# CameraSliderV1.net
KiCad netlist of a schematic drawn in EAGLE
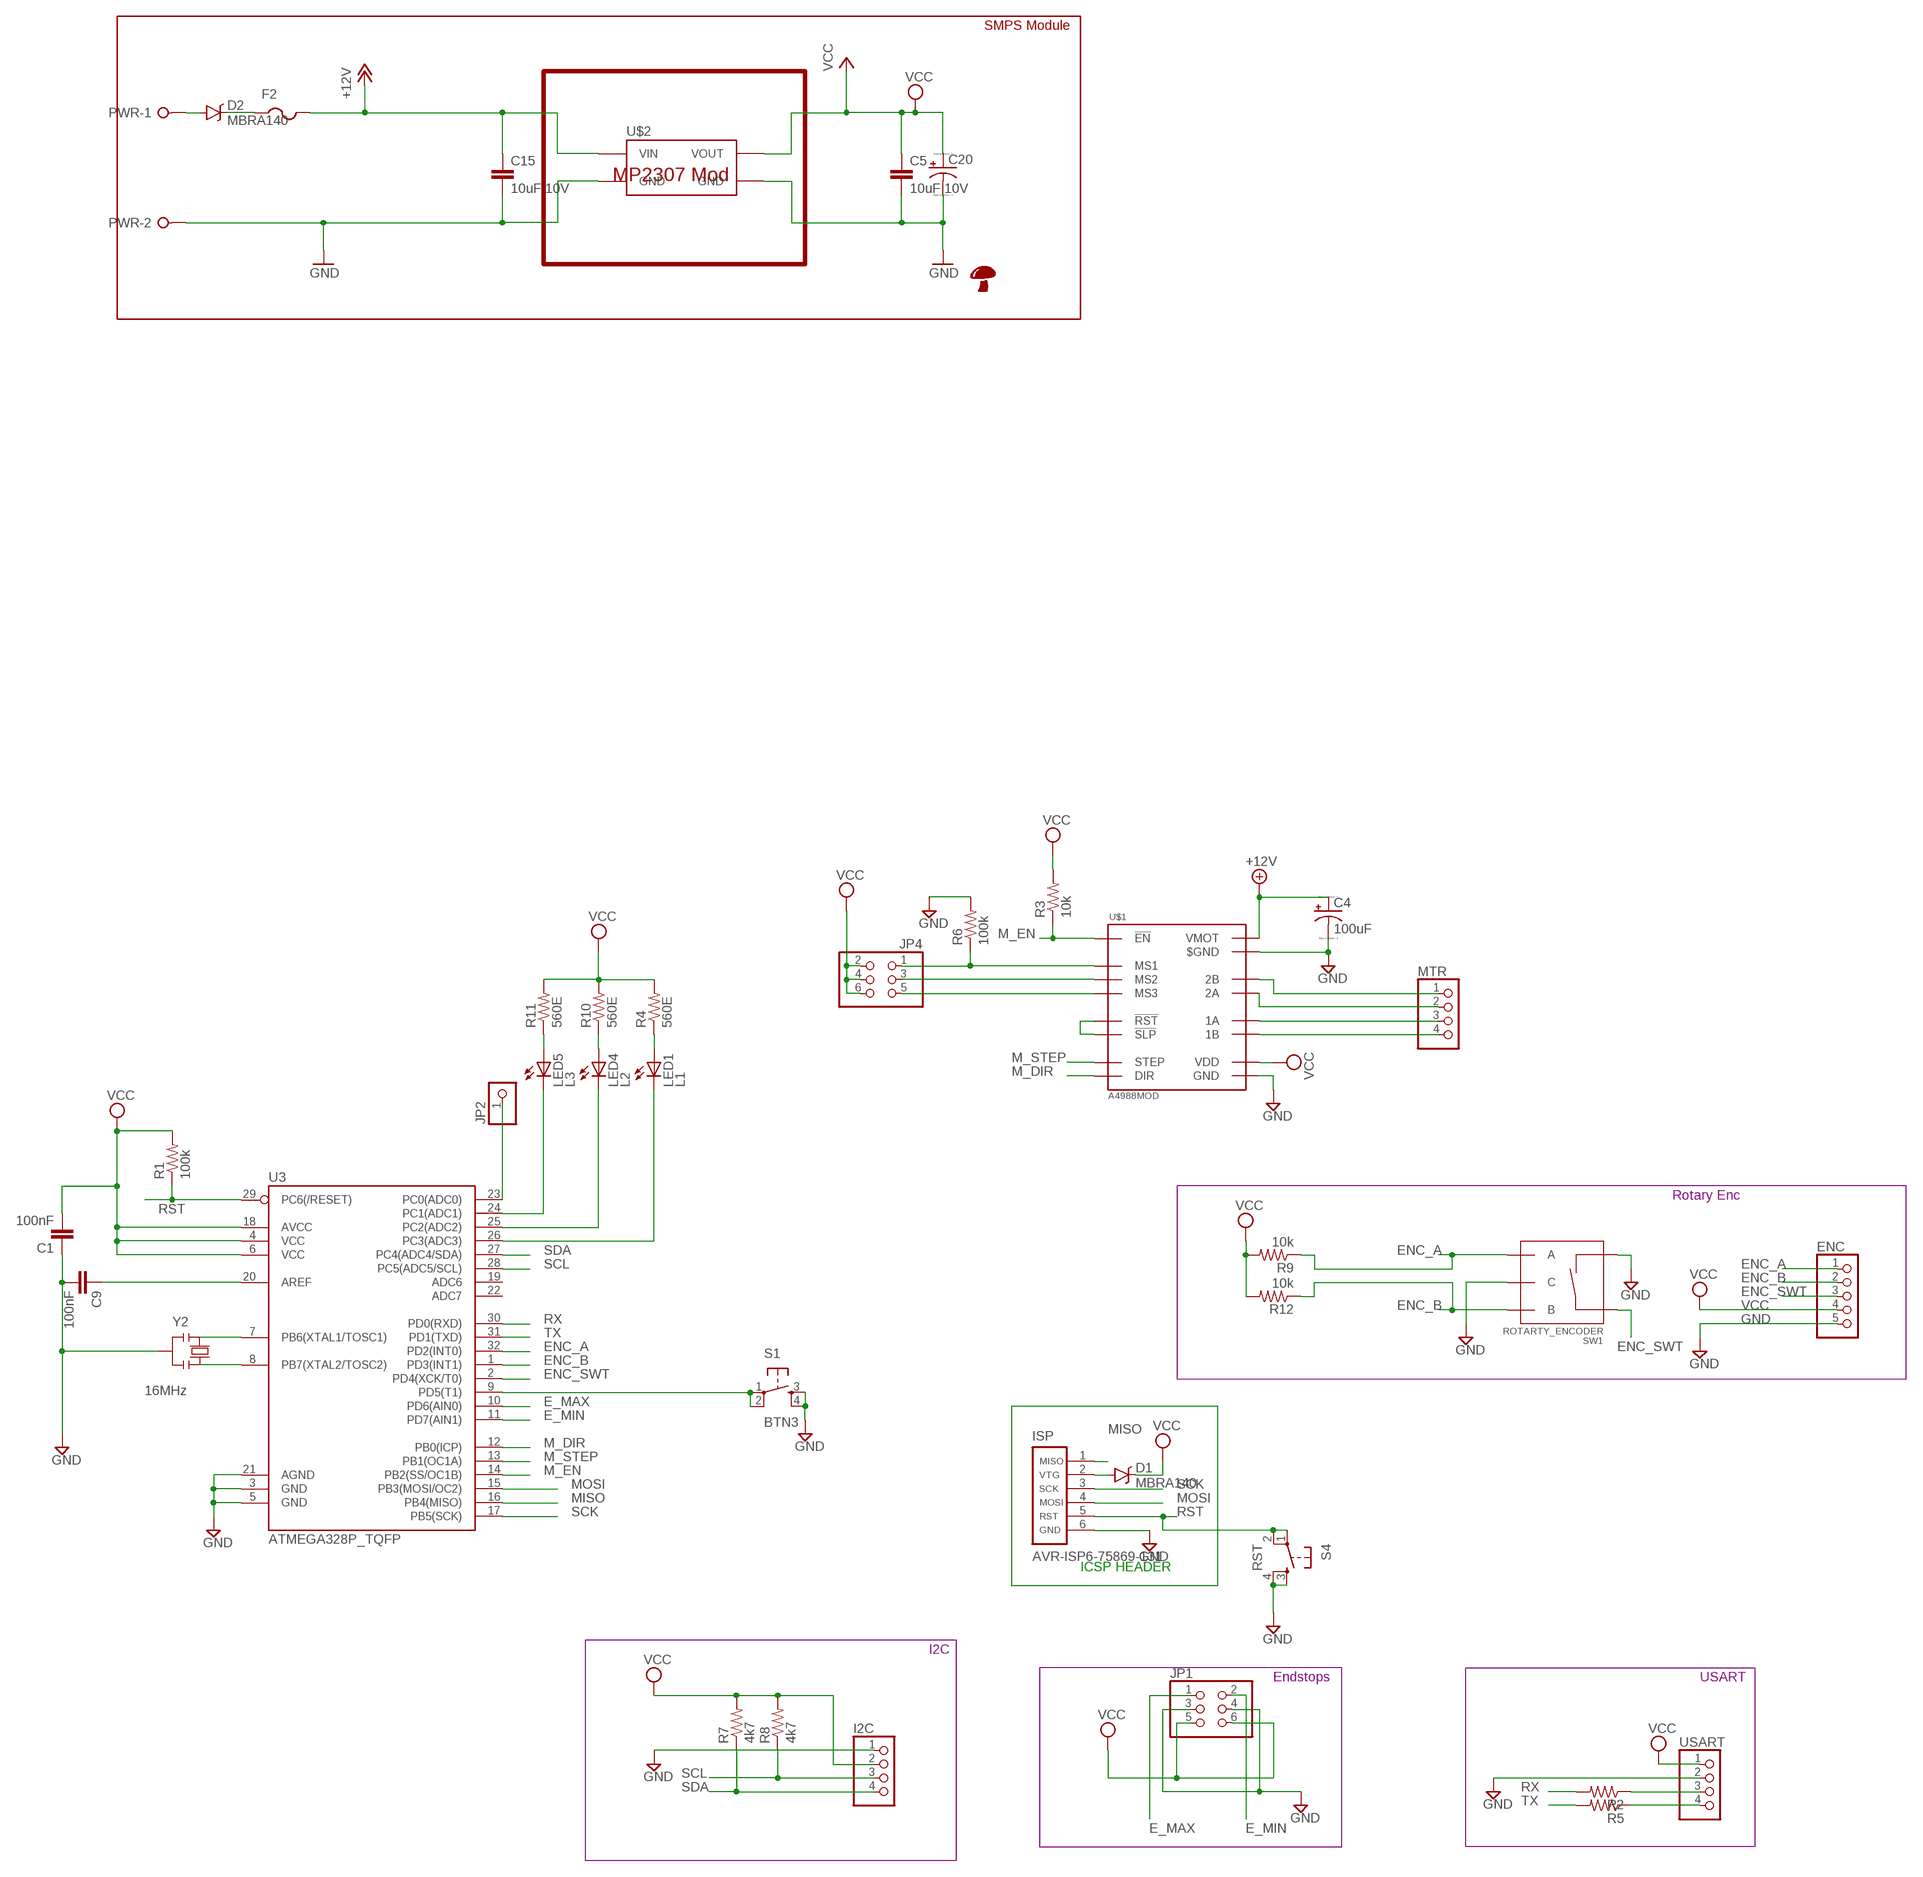
[diagram p0: schematic, sheet 1]

(export (version "E")
  (design (tool "Eeschema 10.0.6"))
  (components
    (comp (ref "C1")
      (value "100nF")
      (footprint "eagle-import:C0805")
      (libsource (lib "eagle-import") (part "C-EUC0805"))
    )
    (comp (ref "C4")
      (value "100uF")
      (footprint "eagle-import:PANASONIC_D")
      (libsource (lib "eagle-import") (part "CPOL-USD"))
    )
    (comp (ref "C5")
      (value "10uF 10V")
      (footprint "eagle-import:C0805")
      (libsource (lib "eagle-import") (part "C-EUC0805"))
    )
    (comp (ref "C9")
      (value "100nF")
      (footprint "eagle-import:C0805")
      (libsource (lib "eagle-import") (part "C-EUC0805"))
    )
    (comp (ref "C15")
      (value "10uF 10V")
      (footprint "eagle-import:C0805")
      (libsource (lib "eagle-import") (part "C-EUC0805"))
    )
    (comp (ref "C20")
      (value "CPOL-USD")
      (footprint "eagle-import:PANASONIC_D")
      (libsource (lib "eagle-import") (part "CPOL-USD"))
    )
    (comp (ref "D1")
      (value "MBRA140")
      (footprint "eagle-import:SMA-DIODE")
      (libsource (lib "eagle-import") (part "MBRA140"))
    )
    (comp (ref "D2")
      (value "MBRA140")
      (footprint "eagle-import:SMA-DIODE")
      (libsource (lib "eagle-import") (part "MBRA140"))
    )
    (comp (ref "ENC")
      (value "PINHD-1X5")
      (footprint "eagle-import:1X05")
      (libsource (lib "eagle-import") (part "PINHD-1X5"))
    )
    (comp (ref "F2")
      (value "PTCFUSE-1812")
      (footprint "eagle-import:1812")
      (libsource (lib "eagle-import") (part "PTCFUSE-1812"))
    )
    (comp (ref "I2C")
      (value "PINHD-1X4")
      (footprint "eagle-import:1X04")
      (libsource (lib "eagle-import") (part "PINHD-1X4"))
    )
    (comp (ref "ISP")
      (value "AVR-ISP6-75869-131")
      (footprint "eagle-import:HDR-75869-131")
      (libsource (lib "eagle-import") (part "AVR-ISP6-75869-131"))
    )
    (comp (ref "JP1")
      (value "PINHD-2X3")
      (footprint "eagle-import:2X03")
      (libsource (lib "eagle-import") (part "PINHD-2X3"))
    )
    (comp (ref "JP2")
      (value "PINHD-1X1")
      (footprint "eagle-import:1X01")
      (libsource (lib "eagle-import") (part "PINHD-1X1"))
    )
    (comp (ref "JP4")
      (value "PINHD-2X3")
      (footprint "eagle-import:2X03")
      (libsource (lib "eagle-import") (part "PINHD-2X3"))
    )
    (comp (ref "LED1")
      (value "L1")
      (footprint "eagle-import:CHIP-LED0805")
      (libsource (lib "eagle-import") (part "LEDCHIP-LED0805"))
    )
    (comp (ref "LED4")
      (value "L2")
      (footprint "eagle-import:CHIP-LED0805")
      (libsource (lib "eagle-import") (part "LEDCHIP-LED0805"))
    )
    (comp (ref "LED5")
      (value "L3")
      (footprint "eagle-import:CHIP-LED0805")
      (libsource (lib "eagle-import") (part "LEDCHIP-LED0805"))
    )
    (comp (ref "MTR")
      (value "PINHD-1X4")
      (footprint "eagle-import:1X04")
      (libsource (lib "eagle-import") (part "PINHD-1X4"))
    )
    (comp (ref "PWR")
      (value "W237-02P")
      (footprint "eagle-import:W237-132")
      (libsource (lib "eagle-import") (part "W237-02P"))
    )
    (comp (ref "R1")
      (value "100k")
      (footprint "eagle-import:M0805")
      (libsource (lib "eagle-import") (part "R-US_M0805"))
    )
    (comp (ref "R2")
      (value "R-US_M0805")
      (footprint "eagle-import:M0805")
      (libsource (lib "eagle-import") (part "R-US_M0805"))
    )
    (comp (ref "R3")
      (value "10k")
      (footprint "eagle-import:M0805")
      (libsource (lib "eagle-import") (part "R-US_M0805"))
    )
    (comp (ref "R4")
      (value "560E")
      (footprint "eagle-import:M0805")
      (libsource (lib "eagle-import") (part "R-US_M0805"))
    )
    (comp (ref "R5")
      (value "R-US_M0805")
      (footprint "eagle-import:M0805")
      (libsource (lib "eagle-import") (part "R-US_M0805"))
    )
    (comp (ref "R6")
      (value "100k")
      (footprint "eagle-import:M0805")
      (libsource (lib "eagle-import") (part "R-US_M0805"))
    )
    (comp (ref "R7")
      (value "4k7")
      (footprint "eagle-import:M0805")
      (libsource (lib "eagle-import") (part "R-US_M0805"))
    )
    (comp (ref "R8")
      (value "4k7")
      (footprint "eagle-import:M0805")
      (libsource (lib "eagle-import") (part "R-US_M0805"))
    )
    (comp (ref "R9")
      (value "10k")
      (footprint "eagle-import:M0805")
      (libsource (lib "eagle-import") (part "R-US_M0805"))
    )
    (comp (ref "R10")
      (value "560E")
      (footprint "eagle-import:M0805")
      (libsource (lib "eagle-import") (part "R-US_M0805"))
    )
    (comp (ref "R11")
      (value "560E")
      (footprint "eagle-import:M0805")
      (libsource (lib "eagle-import") (part "R-US_M0805"))
    )
    (comp (ref "R12")
      (value "10k")
      (footprint "eagle-import:M0805")
      (libsource (lib "eagle-import") (part "R-US_M0805"))
    )
    (comp (ref "S1")
      (value "BTN3")
      (footprint "eagle-import:TACTILE_SWITCH_SMD")
      (libsource (lib "eagle-import") (part "TAC_SWITCHSMD"))
    )
    (comp (ref "S4")
      (value "RST")
      (footprint "eagle-import:TACTILE_SWITCH_SMD")
      (libsource (lib "eagle-import") (part "TAC_SWITCHSMD"))
    )
    (comp (ref "SW1")
      (value "ROTARTY_ENCODER")
      (footprint "eagle-import:ROTARY_ENC_PLAIN")
      (libsource (lib "eagle-import") (part "ROTARTY_ENCODER"))
    )
    (comp (ref "U$1")
      (value "A4988MOD")
      (footprint "eagle-import:A4988MOD")
      (libsource (lib "eagle-import") (part "A4988MOD"))
    )
    (comp (ref "U$2")
      (value "MP1584_MODULE")
      (footprint "eagle-import:D-SUN_MP1584")
      (libsource (lib "eagle-import") (part "MP1584_MODULE"))
    )
    (comp (ref "U$15")
      (value "SHROOM5MM")
      (footprint "eagle-import:SHROOM")
      (libsource (lib "eagle-import") (part "SHROOM5MM"))
    )
    (comp (ref "U3")
      (value "ATMEGA328P_TQFP")
      (footprint "eagle-import:TQFP32-08")
      (libsource (lib "eagle-import") (part "ATMEGA328P_TQFP"))
    )
    (comp (ref "USART")
      (value "PINHD-1X4")
      (footprint "eagle-import:1X04")
      (libsource (lib "eagle-import") (part "PINHD-1X4"))
    )
    (comp (ref "Y2")
      (value "16MHz")
      (footprint "eagle-import:RESONATOR")
      (libsource (lib "eagle-import") (part "RESONATORMU"))
    )
  )
  (nets
    (net (code "1") (name "+12V") (class "Default")
      (node (ref "C15") (pin "1") (pinfunction "1_1") (pintype "passive"))
      (node (ref "C4") (pin "+") (pinfunction "+_+") (pintype "passive"))
      (node (ref "F2") (pin "2") (pinfunction "2_2") (pintype "passive"))
      (node (ref "U$1") (pin "P$16") (pinfunction "VMOT_P$16") (pintype "bidirectional"))
      (node (ref "U$2") (pin "P$5") (pinfunction "VIN_P$5") (pintype "input"))
      (node (ref "U$2") (pin "P$6") (pinfunction "VIN_P$6") (pintype "input"))
    )
    (net (code "2") (name "/ENC_A") (class "Default")
      (node (ref "ENC") (pin "1") (pinfunction "1_1") (pintype "passive"))
      (node (ref "R9") (pin "1") (pinfunction "1_1") (pintype "passive"))
      (node (ref "SW1") (pin "A") (pinfunction "A_A") (pintype "bidirectional"))
      (node (ref "U3") (pin "32") (pinfunction "PD2(INT0)_32") (pintype "bidirectional"))
    )
    (net (code "3") (name "/ENC_B") (class "Default")
      (node (ref "ENC") (pin "2") (pinfunction "2_2") (pintype "passive"))
      (node (ref "R12") (pin "1") (pinfunction "1_1") (pintype "passive"))
      (node (ref "SW1") (pin "B") (pinfunction "B_B") (pintype "bidirectional"))
      (node (ref "U3") (pin "1") (pinfunction "PD3(INT1)_1") (pintype "bidirectional"))
    )
    (net (code "4") (name "/ENC_SWT") (class "Default")
      (node (ref "ENC") (pin "3") (pinfunction "3_3") (pintype "passive"))
      (node (ref "SW1") (pin "SW+") (pinfunction "SW+_SW+") (pintype "bidirectional"))
      (node (ref "U3") (pin "2") (pinfunction "PD4(XCK/T0)_2") (pintype "bidirectional"))
    )
    (net (code "5") (name "/E_MAX") (class "Default")
      (node (ref "JP1") (pin "1") (pinfunction "1_1") (pintype "passive"))
      (node (ref "U3") (pin "10") (pinfunction "PD6(AIN0)_10") (pintype "bidirectional"))
    )
    (net (code "6") (name "/E_MIN") (class "Default")
      (node (ref "JP1") (pin "2") (pinfunction "2_2") (pintype "passive"))
      (node (ref "U3") (pin "11") (pinfunction "PD7(AIN1)_11") (pintype "bidirectional"))
    )
    (net (code "7") (name "/MISO") (class "Default")
      (node (ref "ISP") (pin "1") (pinfunction "1_1") (pintype "passive"))
      (node (ref "U3") (pin "16") (pinfunction "PB4(MISO)_16") (pintype "bidirectional"))
    )
    (net (code "8") (name "/MOSI") (class "Default")
      (node (ref "ISP") (pin "4") (pinfunction "4_4") (pintype "passive"))
      (node (ref "U3") (pin "15") (pinfunction "PB3(MOSI/OC2)_15") (pintype "bidirectional"))
    )
    (net (code "9") (name "/M_DIR") (class "Default")
      (node (ref "U$1") (pin "P$8") (pinfunction "DIR_P$8") (pintype "bidirectional"))
      (node (ref "U3") (pin "12") (pinfunction "PB0(ICP)_12") (pintype "bidirectional"))
    )
    (net (code "10") (name "/M_EN") (class "Default")
      (node (ref "R3") (pin "1") (pinfunction "1_1") (pintype "passive"))
      (node (ref "U$1") (pin "P$1") (pinfunction "~{EN}_P$1") (pintype "bidirectional"))
      (node (ref "U3") (pin "14") (pinfunction "PB2(SS/OC1B)_14") (pintype "bidirectional"))
    )
    (net (code "11") (name "/M_STEP") (class "Default")
      (node (ref "U$1") (pin "P$7") (pinfunction "STEP_P$7") (pintype "bidirectional"))
      (node (ref "U3") (pin "13") (pinfunction "PB1(OC1A)_13") (pintype "bidirectional"))
    )
    (net (code "12") (name "/RST") (class "Default")
      (node (ref "ISP") (pin "5") (pinfunction "5_5") (pintype "passive"))
      (node (ref "R1") (pin "1") (pinfunction "1_1") (pintype "passive"))
      (node (ref "S4") (pin "1") (pinfunction "1_1") (pintype "passive"))
      (node (ref "S4") (pin "2") (pinfunction "2_2") (pintype "passive"))
      (node (ref "U3") (pin "29") (pinfunction "PC6(/RESET)_29") (pintype "bidirectional"))
    )
    (net (code "13") (name "/RX") (class "Default")
      (node (ref "R2") (pin "2") (pinfunction "2_2") (pintype "passive"))
      (node (ref "U3") (pin "30") (pinfunction "PD0(RXD)_30") (pintype "bidirectional"))
    )
    (net (code "14") (name "/SCK") (class "Default")
      (node (ref "ISP") (pin "3") (pinfunction "3_3") (pintype "passive"))
      (node (ref "U3") (pin "17") (pinfunction "PB5(SCK)_17") (pintype "bidirectional"))
    )
    (net (code "15") (name "/SCL") (class "Default")
      (node (ref "I2C") (pin "3") (pinfunction "3_3") (pintype "passive"))
      (node (ref "R8") (pin "1") (pinfunction "1_1") (pintype "passive"))
      (node (ref "U3") (pin "28") (pinfunction "PC5(ADC5/SCL)_28") (pintype "bidirectional"))
    )
    (net (code "16") (name "/SDA") (class "Default")
      (node (ref "I2C") (pin "4") (pinfunction "4_4") (pintype "passive"))
      (node (ref "R7") (pin "1") (pinfunction "1_1") (pintype "passive"))
      (node (ref "U3") (pin "27") (pinfunction "PC4(ADC4/SDA)_27") (pintype "bidirectional"))
    )
    (net (code "17") (name "/TX") (class "Default")
      (node (ref "R5") (pin "2") (pinfunction "2_2") (pintype "passive"))
      (node (ref "U3") (pin "31") (pinfunction "PD1(TXD)_31") (pintype "bidirectional"))
    )
    (net (code "18") (name "GND") (class "Default")
      (node (ref "C1") (pin "1") (pinfunction "1_1") (pintype "passive"))
      (node (ref "C15") (pin "2") (pinfunction "2_2") (pintype "passive"))
      (node (ref "C20") (pin "-") (pinfunction "-_-") (pintype "passive"))
      (node (ref "C4") (pin "-") (pinfunction "-_-") (pintype "passive"))
      (node (ref "C5") (pin "2") (pinfunction "2_2") (pintype "passive"))
      (node (ref "C9") (pin "2") (pinfunction "2_2") (pintype "passive"))
      (node (ref "ENC") (pin "5") (pinfunction "5_5") (pintype "passive"))
      (node (ref "I2C") (pin "1") (pinfunction "1_1") (pintype "passive"))
      (node (ref "ISP") (pin "6") (pinfunction "6_6") (pintype "passive"))
      (node (ref "JP1") (pin "3") (pinfunction "3_3") (pintype "passive"))
      (node (ref "JP1") (pin "4") (pinfunction "4_4") (pintype "passive"))
      (node (ref "PWR") (pin "2") (pinfunction "KL_2") (pintype "passive"))
      (node (ref "R6") (pin "2") (pinfunction "2_2") (pintype "passive"))
      (node (ref "S1") (pin "3") (pinfunction "3_3") (pintype "passive"))
      (node (ref "S1") (pin "4") (pinfunction "4_4") (pintype "passive"))
      (node (ref "S4") (pin "3") (pinfunction "3_3") (pintype "passive"))
      (node (ref "S4") (pin "4") (pinfunction "4_4") (pintype "passive"))
      (node (ref "SW1") (pin "C") (pinfunction "C_C") (pintype "bidirectional"))
      (node (ref "SW1") (pin "SW-") (pinfunction "SW-_SW-") (pintype "bidirectional"))
      (node (ref "U$1") (pin "P$15") (pinfunction "$GND_P$15") (pintype "bidirectional"))
      (node (ref "U$1") (pin "P$9") (pinfunction "GND_P$9") (pintype "bidirectional"))
      (node (ref "U$2") (pin "P$1") (pinfunction "GND_P$1") (pintype "bidirectional"))
      (node (ref "U$2") (pin "P$2") (pinfunction "GND_P$2") (pintype "bidirectional"))
      (node (ref "U$2") (pin "P$3") (pinfunction "GND_P$3") (pintype "bidirectional"))
      (node (ref "U$2") (pin "P$4") (pinfunction "GND_P$4") (pintype "bidirectional"))
      (node (ref "U3") (pin "21") (pinfunction "AGND_21") (pintype "bidirectional"))
      (node (ref "U3") (pin "3") (pinfunction "GND_3") (pintype "bidirectional"))
      (node (ref "U3") (pin "5") (pinfunction "GND_5") (pintype "bidirectional"))
      (node (ref "USART") (pin "2") (pinfunction "2_2") (pintype "passive"))
      (node (ref "Y2") (pin "2") (pinfunction "2_2") (pintype "passive"))
    )
    (net (code "19") (name "Net-(D1-PadA)") (class "Default")
      (node (ref "D1") (pin "A") (pinfunction "A_A") (pintype "passive"))
      (node (ref "ISP") (pin "2") (pinfunction "2_2") (pintype "passive"))
    )
    (net (code "20") (name "Net-(D2-PadC)") (class "Default")
      (node (ref "D2") (pin "C") (pinfunction "C_C") (pintype "passive"))
      (node (ref "F2") (pin "1") (pinfunction "1_1") (pintype "passive"))
    )
    (net (code "21") (name "Net-(LED1-PadA)") (class "Default")
      (node (ref "LED1") (pin "A") (pinfunction "A_A") (pintype "passive"))
      (node (ref "R4") (pin "1") (pinfunction "1_1") (pintype "passive"))
    )
    (net (code "22") (name "Net-(LED4-PadA)") (class "Default")
      (node (ref "LED4") (pin "A") (pinfunction "A_A") (pintype "passive"))
      (node (ref "R10") (pin "1") (pinfunction "1_1") (pintype "passive"))
    )
    (net (code "23") (name "Net-(LED5-PadA)") (class "Default")
      (node (ref "LED5") (pin "A") (pinfunction "A_A") (pintype "passive"))
      (node (ref "R11") (pin "1") (pinfunction "1_1") (pintype "passive"))
    )
    (net (code "24") (name "Net-(PWRA-KL)") (class "Default")
      (node (ref "D2") (pin "A") (pinfunction "A_A") (pintype "passive"))
      (node (ref "PWR") (pin "1") (pinfunction "KL_1") (pintype "passive"))
    )
    (net (code "25") (name "Net-(R2-Pad1)") (class "Default")
      (node (ref "R2") (pin "1") (pinfunction "1_1") (pintype "passive"))
      (node (ref "USART") (pin "3") (pinfunction "3_3") (pintype "passive"))
    )
    (net (code "26") (name "Net-(R5-Pad1)") (class "Default")
      (node (ref "R5") (pin "1") (pinfunction "1_1") (pintype "passive"))
      (node (ref "USART") (pin "4") (pinfunction "4_4") (pintype "passive"))
    )
    (net (code "27") (name "Net-(U$1-1A)") (class "Default")
      (node (ref "MTR") (pin "3") (pinfunction "3_3") (pintype "passive"))
      (node (ref "U$1") (pin "P$12") (pinfunction "1A_P$12") (pintype "bidirectional"))
    )
    (net (code "28") (name "Net-(U$1-1B)") (class "Default")
      (node (ref "MTR") (pin "4") (pinfunction "4_4") (pintype "passive"))
      (node (ref "U$1") (pin "P$11") (pinfunction "1B_P$11") (pintype "bidirectional"))
    )
    (net (code "29") (name "Net-(U$1-2A)") (class "Default")
      (node (ref "MTR") (pin "2") (pinfunction "2_2") (pintype "passive"))
      (node (ref "U$1") (pin "P$13") (pinfunction "2A_P$13") (pintype "bidirectional"))
    )
    (net (code "30") (name "Net-(U$1-2B)") (class "Default")
      (node (ref "MTR") (pin "1") (pinfunction "1_1") (pintype "passive"))
      (node (ref "U$1") (pin "P$14") (pinfunction "2B_P$14") (pintype "bidirectional"))
    )
    (net (code "31") (name "Net-(U$1-MS1)") (class "Default")
      (node (ref "JP4") (pin "1") (pinfunction "1_1") (pintype "passive"))
      (node (ref "R6") (pin "1") (pinfunction "1_1") (pintype "passive"))
      (node (ref "U$1") (pin "P$2") (pinfunction "MS1_P$2") (pintype "bidirectional"))
    )
    (net (code "32") (name "Net-(U$1-MS2)") (class "Default")
      (node (ref "JP4") (pin "3") (pinfunction "3_3") (pintype "passive"))
      (node (ref "U$1") (pin "P$3") (pinfunction "MS2_P$3") (pintype "bidirectional"))
    )
    (net (code "33") (name "Net-(U$1-MS3)") (class "Default")
      (node (ref "JP4") (pin "5") (pinfunction "5_5") (pintype "passive"))
      (node (ref "U$1") (pin "P$4") (pinfunction "MS3_P$4") (pintype "bidirectional"))
    )
    (net (code "34") (name "Net-(U$1-~{RST})") (class "Default")
      (node (ref "U$1") (pin "P$5") (pinfunction "~{RST}_P$5") (pintype "bidirectional"))
      (node (ref "U$1") (pin "P$6") (pinfunction "~{SLP}_P$6") (pintype "bidirectional"))
    )
    (net (code "35") (name "Net-(U3-AREF)") (class "Default")
      (node (ref "C9") (pin "1") (pinfunction "1_1") (pintype "passive"))
      (node (ref "U3") (pin "20") (pinfunction "AREF_20") (pintype "bidirectional"))
    )
    (net (code "36") (name "Net-(U3-PB6(XTAL1{slash}TOSC1))") (class "Default")
      (node (ref "U3") (pin "7") (pinfunction "PB6(XTAL1/TOSC1)_7") (pintype "bidirectional"))
      (node (ref "Y2") (pin "1") (pinfunction "1_1") (pintype "passive"))
    )
    (net (code "37") (name "Net-(U3-PB7(XTAL2{slash}TOSC2))") (class "Default")
      (node (ref "U3") (pin "8") (pinfunction "PB7(XTAL2/TOSC2)_8") (pintype "bidirectional"))
      (node (ref "Y2") (pin "3") (pinfunction "3_3") (pintype "passive"))
    )
    (net (code "38") (name "Net-(U3-PC0(ADC0))") (class "Default")
      (node (ref "JP2") (pin "1") (pinfunction "1_1") (pintype "passive"))
      (node (ref "U3") (pin "23") (pinfunction "PC0(ADC0)_23") (pintype "bidirectional"))
    )
    (net (code "39") (name "Net-(U3-PC1(ADC1))") (class "Default")
      (node (ref "LED5") (pin "C") (pinfunction "C_C") (pintype "passive"))
      (node (ref "U3") (pin "24") (pinfunction "PC1(ADC1)_24") (pintype "bidirectional"))
    )
    (net (code "40") (name "Net-(U3-PC2(ADC2))") (class "Default")
      (node (ref "LED4") (pin "C") (pinfunction "C_C") (pintype "passive"))
      (node (ref "U3") (pin "25") (pinfunction "PC2(ADC2)_25") (pintype "bidirectional"))
    )
    (net (code "41") (name "Net-(U3-PC3(ADC3))") (class "Default")
      (node (ref "LED1") (pin "C") (pinfunction "C_C") (pintype "passive"))
      (node (ref "U3") (pin "26") (pinfunction "PC3(ADC3)_26") (pintype "bidirectional"))
    )
    (net (code "42") (name "Net-(U3-PD5(T1))") (class "Default")
      (node (ref "S1") (pin "1") (pinfunction "1_1") (pintype "passive"))
      (node (ref "S1") (pin "2") (pinfunction "2_2") (pintype "passive"))
      (node (ref "U3") (pin "9") (pinfunction "PD5(T1)_9") (pintype "bidirectional"))
    )
    (net (code "43") (name "VCC") (class "Default")
      (node (ref "C1") (pin "2") (pinfunction "2_2") (pintype "passive"))
      (node (ref "C20") (pin "+") (pinfunction "+_+") (pintype "passive"))
      (node (ref "C5") (pin "1") (pinfunction "1_1") (pintype "passive"))
      (node (ref "D1") (pin "C") (pinfunction "C_C") (pintype "passive"))
      (node (ref "ENC") (pin "4") (pinfunction "4_4") (pintype "passive"))
      (node (ref "I2C") (pin "2") (pinfunction "2_2") (pintype "passive"))
      (node (ref "JP1") (pin "5") (pinfunction "5_5") (pintype "passive"))
      (node (ref "JP1") (pin "6") (pinfunction "6_6") (pintype "passive"))
      (node (ref "JP4") (pin "2") (pinfunction "2_2") (pintype "passive"))
      (node (ref "JP4") (pin "4") (pinfunction "4_4") (pintype "passive"))
      (node (ref "JP4") (pin "6") (pinfunction "6_6") (pintype "passive"))
      (node (ref "R1") (pin "2") (pinfunction "2_2") (pintype "passive"))
      (node (ref "R10") (pin "2") (pinfunction "2_2") (pintype "passive"))
      (node (ref "R11") (pin "2") (pinfunction "2_2") (pintype "passive"))
      (node (ref "R12") (pin "2") (pinfunction "2_2") (pintype "passive"))
      (node (ref "R3") (pin "2") (pinfunction "2_2") (pintype "passive"))
      (node (ref "R4") (pin "2") (pinfunction "2_2") (pintype "passive"))
      (node (ref "R7") (pin "2") (pinfunction "2_2") (pintype "passive"))
      (node (ref "R8") (pin "2") (pinfunction "2_2") (pintype "passive"))
      (node (ref "R9") (pin "2") (pinfunction "2_2") (pintype "passive"))
      (node (ref "U$1") (pin "P$10") (pinfunction "VDD_P$10") (pintype "bidirectional"))
      (node (ref "U$2") (pin "P$7") (pinfunction "VOUT_P$7") (pintype "output"))
      (node (ref "U$2") (pin "P$8") (pinfunction "VOUT_P$8") (pintype "output"))
      (node (ref "U3") (pin "18") (pinfunction "AVCC_18") (pintype "bidirectional"))
      (node (ref "U3") (pin "4") (pinfunction "VCC_4") (pintype "bidirectional"))
      (node (ref "U3") (pin "6") (pinfunction "VCC_6") (pintype "bidirectional"))
      (node (ref "USART") (pin "1") (pinfunction "1_1") (pintype "passive"))
    )
    (net (code "44") (name "unconnected-(U3-ADC6-Pad19)") (class "Default")
      (node (ref "U3") (pin "19") (pinfunction "ADC6_19") (pintype "bidirectional"))
    )
    (net (code "45") (name "unconnected-(U3-ADC7-Pad22)") (class "Default")
      (node (ref "U3") (pin "22") (pinfunction "ADC7_22") (pintype "bidirectional"))
    )
  )
)
